# tamagotchi.net
KiCad netlist of a schematic drawn in EAGLE
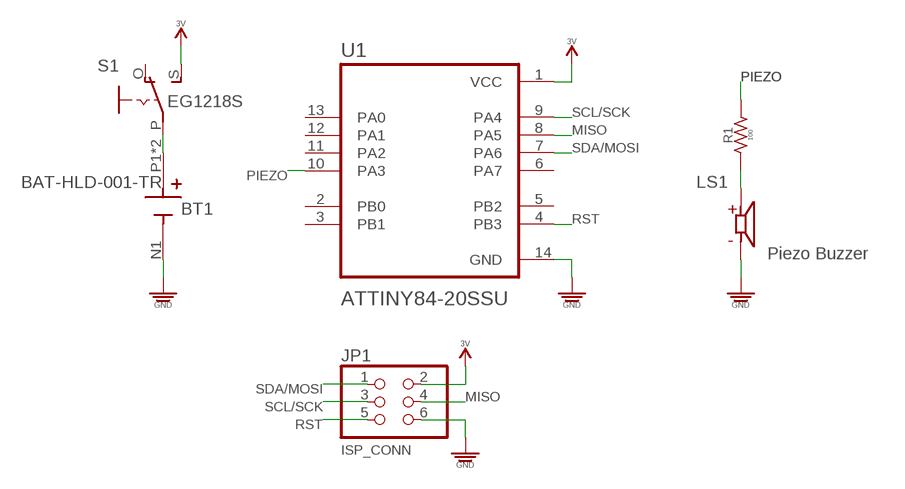
[diagram p0: schematic, sheet 1]

(export (version "E")
  (design (tool "Eeschema 10.0.6"))
  (components
    (comp (ref "BT1")
      (value "BAT-HLD-001-TR")
      (footprint "eagle-import:BAT_BAT-HLD-001-TR")
      (fields
        (field (name "DIGI-KEY_PART_NUMBER") "BAT-HLD-001-TRTR-ND")
        (field (name "MF") "Linx Technologies")
      )
      (libsource (lib "eagle-import") (part "BAT-HLD-001-TR"))
    )
    (comp (ref "JP1")
      (value "PINHD-2X3")
      (footprint "eagle-import:2X03")
      (libsource (lib "eagle-import") (part "PINHD-2X3"))
    )
    (comp (ref "LS1")
      (value "Piezo Buzzer")
      (footprint "eagle-import:CUI_CSS-0575A-SMT")
      (fields
        (field (name "DIGI-KEY_PART_NUMBER") "102-2201-2-ND")
        (field (name "MF") "CUI Devices")
        (field (name "MP") "CSS-0575A-SMT-TR")
      )
      (libsource (lib "eagle-import") (part "CSS-0575A-SMT"))
    )
    (comp (ref "R1")
      (value "100")
      (footprint "eagle-import:RESC2012X60_SMD-0805")
      (fields (field (name "MFR") "Yageo") (field (name "MPN") "AC0805JR-07100RL"))
      (libsource (lib "eagle-import") (part "100Ω_SMD-0805_1/8W-5%"))
    )
    (comp (ref "S1")
      (value "EG1218S")
      (footprint "eagle-import:EG1218")
      (fields
        (field (name "DIGI-KEY_PART_NUMBER") "EG1903-ND")
        (field (name "MF") "E-Switch")
        (field (name "MP") "EG1218")
      )
      (libsource (lib "eagle-import") (part "EG1218S"))
    )
    (comp (ref "U1")
      (value "ATTINY84-20SSU")
      (footprint "eagle-import:SOIC127P600X175-14N")
      (fields
        (field (name "DIGI-KEY_PART_NUMBER") "ATTINY84-20SSU-ND")
        (field (name "MF") "Microchip Technology / Atmel")
      )
      (libsource (lib "eagle-import") (part "ATTINY84-20SSU"))
    )
  )
  (nets
    (net (code "1") (name "/MISO") (class "Default")
      (node (ref "JP1") (pin "4") (pinfunction "4_4") (pintype "passive"))
      (node (ref "U1") (pin "8") (pinfunction "PA5_8") (pintype "bidirectional"))
    )
    (net (code "2") (name "/PIEZO") (class "Default")
      (node (ref "R1") (pin "2") (pinfunction "2_2") (pintype "passive"))
      (node (ref "U1") (pin "10") (pinfunction "PA3_10") (pintype "bidirectional"))
    )
    (net (code "3") (name "/RST") (class "Default")
      (node (ref "JP1") (pin "5") (pinfunction "5_5") (pintype "passive"))
      (node (ref "U1") (pin "4") (pinfunction "PB3_4") (pintype "bidirectional"))
    )
    (net (code "4") (name "/SCL{slash}SCK") (class "Default")
      (node (ref "JP1") (pin "3") (pinfunction "3_3") (pintype "passive"))
      (node (ref "U1") (pin "9") (pinfunction "PA4_9") (pintype "bidirectional"))
    )
    (net (code "5") (name "/SDA{slash}MOSI") (class "Default")
      (node (ref "JP1") (pin "1") (pinfunction "1_1") (pintype "passive"))
      (node (ref "U1") (pin "7") (pinfunction "PA6_7") (pintype "bidirectional"))
    )
    (net (code "6") (name "3V") (class "Default")
      (node (ref "JP1") (pin "2") (pinfunction "2_2") (pintype "passive"))
      (node (ref "S1") (pin "S") (pinfunction "S_S") (pintype "passive"))
      (node (ref "U1") (pin "1") (pinfunction "VCC_1") (pintype "power_in"))
    )
    (net (code "7") (name "GND") (class "Default")
      (node (ref "BT1") (pin "N1") (pinfunction "-_N1") (pintype "passive"))
      (node (ref "JP1") (pin "6") (pinfunction "6_6") (pintype "passive"))
      (node (ref "LS1") (pin "2") (pinfunction "N_2") (pintype "passive"))
      (node (ref "U1") (pin "14") (pinfunction "GND_14") (pintype "power_in"))
    )
    (net (code "8") (name "Net-(BT1-+-PadP1)") (class "Default")
      (node (ref "BT1") (pin "P1") (pinfunction "+_P1") (pintype "passive"))
      (node (ref "BT1") (pin "P2") (pinfunction "+_P2") (pintype "passive"))
      (node (ref "S1") (pin "P") (pinfunction "P_P") (pintype "passive"))
    )
    (net (code "9") (name "Net-(LS1-P)") (class "Default")
      (node (ref "LS1") (pin "1") (pinfunction "P_1") (pintype "passive"))
      (node (ref "R1") (pin "1") (pinfunction "1_1") (pintype "passive"))
    )
    (net (code "10") (name "unconnected-(S1-PadO)") (class "Default")
      (node (ref "S1") (pin "O") (pinfunction "O_O") (pintype "passive"))
    )
    (net (code "11") (name "unconnected-(U1-PA0-Pad13)") (class "Default")
      (node (ref "U1") (pin "13") (pinfunction "PA0_13") (pintype "bidirectional"))
    )
    (net (code "12") (name "unconnected-(U1-PA1-Pad12)") (class "Default")
      (node (ref "U1") (pin "12") (pinfunction "PA1_12") (pintype "bidirectional"))
    )
    (net (code "13") (name "unconnected-(U1-PA2-Pad11)") (class "Default")
      (node (ref "U1") (pin "11") (pinfunction "PA2_11") (pintype "bidirectional"))
    )
    (net (code "14") (name "unconnected-(U1-PA7-Pad6)") (class "Default")
      (node (ref "U1") (pin "6") (pinfunction "PA7_6") (pintype "bidirectional"))
    )
    (net (code "15") (name "unconnected-(U1-PB0-Pad2)") (class "Default")
      (node (ref "U1") (pin "2") (pinfunction "PB0_2") (pintype "bidirectional"))
    )
    (net (code "16") (name "unconnected-(U1-PB1-Pad3)") (class "Default")
      (node (ref "U1") (pin "3") (pinfunction "PB1_3") (pintype "bidirectional"))
    )
    (net (code "17") (name "unconnected-(U1-PB2-Pad5)") (class "Default")
      (node (ref "U1") (pin "5") (pinfunction "PB2_5") (pintype "bidirectional"))
    )
  )
)
